# motorModule.net
KiCad netlist of a schematic drawn in EAGLE
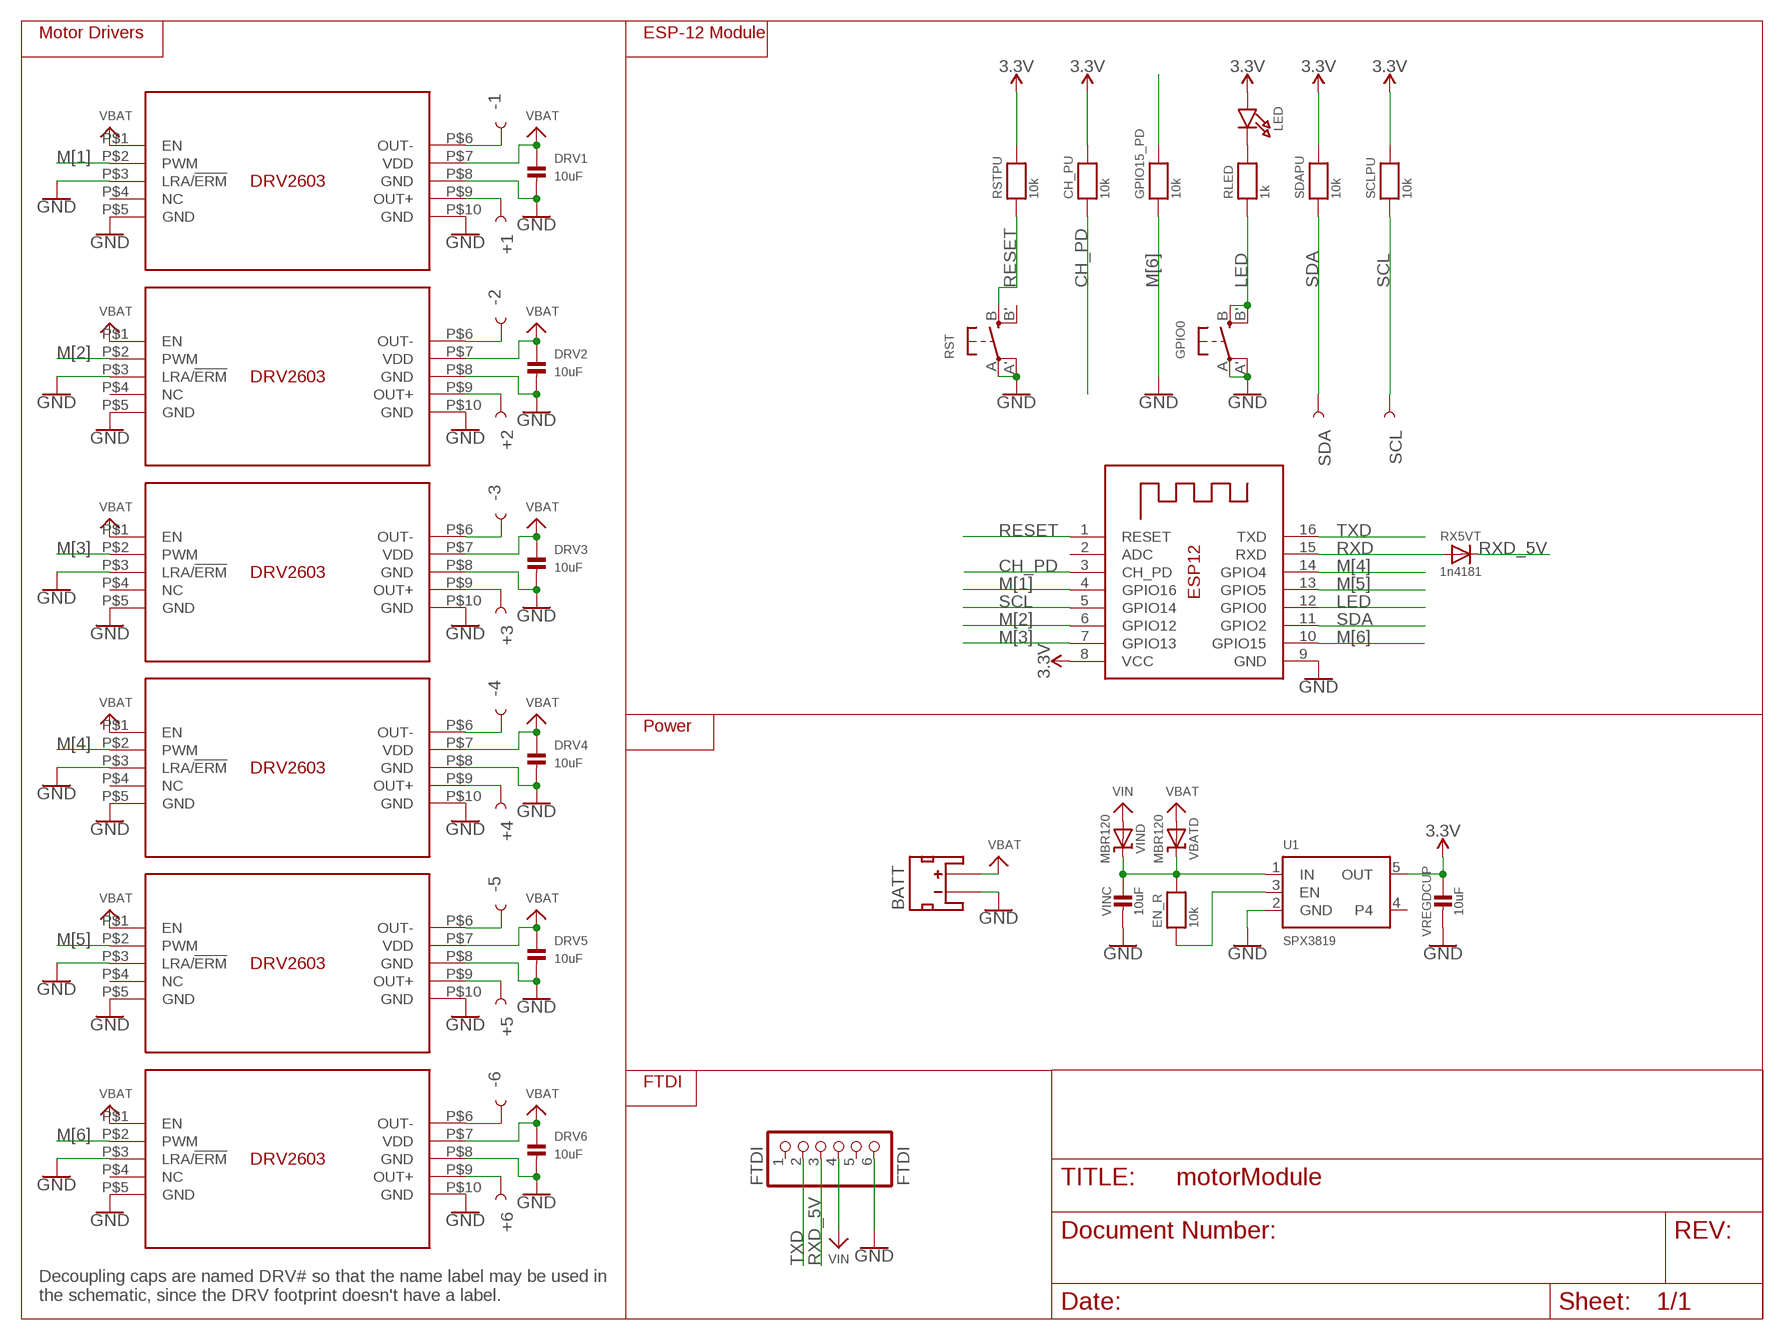
[diagram p0: schematic, sheet 1]

(export (version "E")
  (design (tool "Eeschema 10.0.6"))
  (components
    (comp (ref "+1")
      (value "SEWTAP_SMALL-2SIDE")
      (footprint "eagle-import:PETAL-SMALL-2SIDE")
      (libsource (lib "eagle-import") (part "SEWTAP_SMALL-2SIDE"))
    )
    (comp (ref "+2")
      (value "SEWTAP_SMALL-2SIDE")
      (footprint "eagle-import:PETAL-SMALL-2SIDE")
      (libsource (lib "eagle-import") (part "SEWTAP_SMALL-2SIDE"))
    )
    (comp (ref "+3")
      (value "SEWTAP_SMALL-2SIDE")
      (footprint "eagle-import:PETAL-SMALL-2SIDE")
      (libsource (lib "eagle-import") (part "SEWTAP_SMALL-2SIDE"))
    )
    (comp (ref "+4")
      (value "SEWTAP_SMALL-2SIDE")
      (footprint "eagle-import:PETAL-SMALL-2SIDE")
      (libsource (lib "eagle-import") (part "SEWTAP_SMALL-2SIDE"))
    )
    (comp (ref "+5")
      (value "SEWTAP_SMALL-2SIDE")
      (footprint "eagle-import:PETAL-SMALL-2SIDE")
      (libsource (lib "eagle-import") (part "SEWTAP_SMALL-2SIDE"))
    )
    (comp (ref "+6")
      (value "SEWTAP_SMALL-2SIDE")
      (footprint "eagle-import:PETAL-SMALL-2SIDE")
      (libsource (lib "eagle-import") (part "SEWTAP_SMALL-2SIDE"))
    )
    (comp (ref "-1")
      (value "SEWTAP_SMALL-2SIDE")
      (footprint "eagle-import:PETAL-SMALL-2SIDE")
      (libsource (lib "eagle-import") (part "SEWTAP_SMALL-2SIDE"))
    )
    (comp (ref "-2")
      (value "SEWTAP_SMALL-2SIDE")
      (footprint "eagle-import:PETAL-SMALL-2SIDE")
      (libsource (lib "eagle-import") (part "SEWTAP_SMALL-2SIDE"))
    )
    (comp (ref "-3")
      (value "SEWTAP_SMALL-2SIDE")
      (footprint "eagle-import:PETAL-SMALL-2SIDE")
      (libsource (lib "eagle-import") (part "SEWTAP_SMALL-2SIDE"))
    )
    (comp (ref "-4")
      (value "SEWTAP_SMALL-2SIDE")
      (footprint "eagle-import:PETAL-SMALL-2SIDE")
      (libsource (lib "eagle-import") (part "SEWTAP_SMALL-2SIDE"))
    )
    (comp (ref "-5")
      (value "SEWTAP_SMALL-2SIDE")
      (footprint "eagle-import:PETAL-SMALL-2SIDE")
      (libsource (lib "eagle-import") (part "SEWTAP_SMALL-2SIDE"))
    )
    (comp (ref "-6")
      (value "SEWTAP_SMALL-2SIDE")
      (footprint "eagle-import:PETAL-SMALL-2SIDE")
      (libsource (lib "eagle-import") (part "SEWTAP_SMALL-2SIDE"))
    )
    (comp (ref "BATT")
      (value "JST_2MM_MALE")
      (footprint "eagle-import:JST-2-SMD")
      (libsource (lib "eagle-import") (part "JST_2MM_MALE"))
    )
    (comp (ref "CH_PU")
      (value "10k")
      (footprint "eagle-import:0603")
      (libsource (lib "eagle-import") (part "RESISTOR0603"))
    )
    (comp (ref "DRV1")
      (value "10uF")
      (footprint "eagle-import:0603")
      (libsource (lib "eagle-import") (part "CAP_CERAMIC0603"))
    )
    (comp (ref "DRV2")
      (value "10uF")
      (footprint "eagle-import:0603")
      (libsource (lib "eagle-import") (part "CAP_CERAMIC0603"))
    )
    (comp (ref "DRV3")
      (value "10uF")
      (footprint "eagle-import:0603")
      (libsource (lib "eagle-import") (part "CAP_CERAMIC0603"))
    )
    (comp (ref "DRV4")
      (value "10uF")
      (footprint "eagle-import:0603")
      (libsource (lib "eagle-import") (part "CAP_CERAMIC0603"))
    )
    (comp (ref "DRV5")
      (value "10uF")
      (footprint "eagle-import:0603")
      (libsource (lib "eagle-import") (part "CAP_CERAMIC0603"))
    )
    (comp (ref "DRV6")
      (value "10uF")
      (footprint "eagle-import:0603")
      (libsource (lib "eagle-import") (part "CAP_CERAMIC0603"))
    )
    (comp (ref "DRVIC1")
      (value "DRV2603")
      (footprint "eagle-import:DRV2603")
      (libsource (lib "eagle-import") (part "DRV2603"))
    )
    (comp (ref "DRVIC2")
      (value "DRV2603")
      (footprint "eagle-import:DRV2603")
      (libsource (lib "eagle-import") (part "DRV2603"))
    )
    (comp (ref "DRVIC3")
      (value "DRV2603")
      (footprint "eagle-import:DRV2603")
      (libsource (lib "eagle-import") (part "DRV2603"))
    )
    (comp (ref "DRVIC4")
      (value "DRV2603")
      (footprint "eagle-import:DRV2603")
      (libsource (lib "eagle-import") (part "DRV2603"))
    )
    (comp (ref "DRVIC5")
      (value "DRV2603")
      (footprint "eagle-import:DRV2603")
      (libsource (lib "eagle-import") (part "DRV2603"))
    )
    (comp (ref "DRVIC6")
      (value "DRV2603")
      (footprint "eagle-import:DRV2603")
      (libsource (lib "eagle-import") (part "DRV2603"))
    )
    (comp (ref "EN_R")
      (value "10k")
      (footprint "eagle-import:0603")
      (libsource (lib "eagle-import") (part "RESISTOR0603"))
    )
    (comp (ref "ESP12")
      (value "ESP-12")
      (footprint "eagle-import:ESP-12")
      (libsource (lib "eagle-import") (part "ESP-12"))
    )
    (comp (ref "FTDI")
      (value "FTDI")
      (footprint "eagle-import:1X06")
      (libsource (lib "eagle-import") (part "PINHD-1X6"))
    )
    (comp (ref "GPIO0")
      (value "SWITCH_TACT_SMT4.6X2.8")
      (footprint "eagle-import:BTN_KMR2_4.6X2.8")
      (libsource (lib "eagle-import") (part "SWITCH_TACT_SMT4.6X2.8"))
    )
    (comp (ref "GPIO15_PD")
      (value "10k")
      (footprint "eagle-import:0603")
      (libsource (lib "eagle-import") (part "RESISTOR0603"))
    )
    (comp (ref "LED")
      (value "MICROBUILDER_LED0805")
      (footprint "eagle-import:MICROBUILDER_CHIPLED_0805")
      (libsource (lib "eagle-import") (part "MICROBUILDER_LED0805"))
    )
    (comp (ref "RLED")
      (value "1k")
      (footprint "eagle-import:0603")
      (libsource (lib "eagle-import") (part "RESISTOR0603"))
    )
    (comp (ref "RST")
      (value "SWITCH_TACT_SMT4.6X2.8")
      (footprint "eagle-import:BTN_KMR2_4.6X2.8")
      (libsource (lib "eagle-import") (part "SWITCH_TACT_SMT4.6X2.8"))
    )
    (comp (ref "RSTPU")
      (value "10k")
      (footprint "eagle-import:0603")
      (libsource (lib "eagle-import") (part "RESISTOR0603"))
    )
    (comp (ref "RX5VT")
      (value "1n4181")
      (footprint "eagle-import:MICROBUILDER_SOD-323")
      (libsource (lib "eagle-import") (part "MICROBUILDER_DIODESOD-323"))
    )
    (comp (ref "SCL")
      (value "SEWTAP_SMALL-2SIDE")
      (footprint "eagle-import:PETAL-SMALL-2SIDE")
      (libsource (lib "eagle-import") (part "SEWTAP_SMALL-2SIDE"))
    )
    (comp (ref "SCLPU")
      (value "10k")
      (footprint "eagle-import:0603")
      (libsource (lib "eagle-import") (part "RESISTOR0603"))
    )
    (comp (ref "SDA")
      (value "SEWTAP_SMALL-2SIDE")
      (footprint "eagle-import:PETAL-SMALL-2SIDE")
      (libsource (lib "eagle-import") (part "SEWTAP_SMALL-2SIDE"))
    )
    (comp (ref "SDAPU")
      (value "10k")
      (footprint "eagle-import:0603")
      (libsource (lib "eagle-import") (part "RESISTOR0603"))
    )
    (comp (ref "U1")
      (value "SPX3819")
      (footprint "eagle-import:SOT23-5")
      (libsource (lib "eagle-import") (part "VREG_SOT23-5"))
    )
    (comp (ref "VBATD")
      (value "MBR120")
      (footprint "eagle-import:MICROBUILDER_SOD-123")
      (libsource (lib "eagle-import") (part "MICROBUILDER_DIODE-SCHOTTKYSOD-123"))
    )
    (comp (ref "VINC")
      (value "10uF")
      (footprint "eagle-import:MICROBUILDER_0805-NO")
      (libsource (lib "eagle-import") (part "MICROBUILDER_CAP_CERAMIC0805-NOOUTLINE"))
    )
    (comp (ref "VIND")
      (value "MBR120")
      (footprint "eagle-import:MICROBUILDER_SOD-123")
      (libsource (lib "eagle-import") (part "MICROBUILDER_DIODE-SCHOTTKYSOD-123"))
    )
    (comp (ref "VREGDCUP")
      (value "10uF")
      (footprint "eagle-import:MICROBUILDER_0805-NO")
      (libsource (lib "eagle-import") (part "MICROBUILDER_CAP_CERAMIC0805-NOOUTLINE"))
    )
  )
  (nets
    (net (code "1") (name "/CH_PD") (class "Default")
      (node (ref "CH_PU") (pin "1") (pinfunction "1_1") (pintype "passive"))
      (node (ref "ESP12") (pin "3") (pinfunction "CH_PD_3") (pintype "input"))
    )
    (net (code "2") (name "/LED") (class "Default")
      (node (ref "ESP12") (pin "12") (pinfunction "GPIO0_12") (pintype "bidirectional"))
      (node (ref "GPIO0") (pin "B") (pinfunction "S_B") (pintype "passive"))
      (node (ref "GPIO0") (pin "B'") (pinfunction "S1_B'") (pintype "passive"))
      (node (ref "RLED") (pin "1") (pinfunction "1_1") (pintype "passive"))
    )
    (net (code "3") (name "/M[1]") (class "Default")
      (node (ref "DRVIC1") (pin "P$2") (pinfunction "PWM_P$2") (pintype "bidirectional"))
      (node (ref "ESP12") (pin "4") (pinfunction "GPIO16_4") (pintype "bidirectional"))
    )
    (net (code "4") (name "/M[2]") (class "Default")
      (node (ref "DRVIC2") (pin "P$2") (pinfunction "PWM_P$2") (pintype "bidirectional"))
      (node (ref "ESP12") (pin "6") (pinfunction "GPIO12_6") (pintype "bidirectional"))
    )
    (net (code "5") (name "/M[3]") (class "Default")
      (node (ref "DRVIC3") (pin "P$2") (pinfunction "PWM_P$2") (pintype "bidirectional"))
      (node (ref "ESP12") (pin "7") (pinfunction "GPIO13_7") (pintype "bidirectional"))
    )
    (net (code "6") (name "/M[4]") (class "Default")
      (node (ref "DRVIC4") (pin "P$2") (pinfunction "PWM_P$2") (pintype "bidirectional"))
      (node (ref "ESP12") (pin "14") (pinfunction "GPIO4_14") (pintype "bidirectional"))
    )
    (net (code "7") (name "/M[5]") (class "Default")
      (node (ref "DRVIC5") (pin "P$2") (pinfunction "PWM_P$2") (pintype "bidirectional"))
      (node (ref "ESP12") (pin "13") (pinfunction "GPIO5_13") (pintype "bidirectional"))
    )
    (net (code "8") (name "/M[6]") (class "Default")
      (node (ref "DRVIC6") (pin "P$2") (pinfunction "PWM_P$2") (pintype "bidirectional"))
      (node (ref "ESP12") (pin "10") (pinfunction "GPIO15_10") (pintype "bidirectional"))
      (node (ref "GPIO15_PD") (pin "2") (pinfunction "2_2") (pintype "passive"))
    )
    (net (code "9") (name "/RESET") (class "Default")
      (node (ref "ESP12") (pin "1") (pinfunction "RESET_1") (pintype "input"))
      (node (ref "RST") (pin "B") (pinfunction "S_B") (pintype "passive"))
      (node (ref "RSTPU") (pin "1") (pinfunction "1_1") (pintype "passive"))
    )
    (net (code "10") (name "/RXD") (class "Default")
      (node (ref "ESP12") (pin "15") (pinfunction "RXD_15") (pintype "input"))
      (node (ref "RX5VT") (pin "A") (pinfunction "A_A") (pintype "passive"))
    )
    (net (code "11") (name "/RXD_5V") (class "Default")
      (node (ref "FTDI") (pin "3") (pinfunction "3_3") (pintype "passive"))
      (node (ref "RX5VT") (pin "C") (pinfunction "C_C") (pintype "passive"))
    )
    (net (code "12") (name "/SCL") (class "Default")
      (node (ref "ESP12") (pin "5") (pinfunction "GPIO14_5") (pintype "bidirectional"))
      (node (ref "SCL") (pin "1") (pinfunction "1_1") (pintype "bidirectional"))
      (node (ref "SCLPU") (pin "1") (pinfunction "1_1") (pintype "passive"))
    )
    (net (code "13") (name "/SDA") (class "Default")
      (node (ref "ESP12") (pin "11") (pinfunction "GPIO2_11") (pintype "bidirectional"))
      (node (ref "SDA") (pin "1") (pinfunction "1_1") (pintype "bidirectional"))
      (node (ref "SDAPU") (pin "1") (pinfunction "1_1") (pintype "passive"))
    )
    (net (code "14") (name "/TXD") (class "Default")
      (node (ref "ESP12") (pin "16") (pinfunction "TXD_16") (pintype "output"))
      (node (ref "FTDI") (pin "2") (pinfunction "2_2") (pintype "passive"))
    )
    (net (code "15") (name "3.3V") (class "Default")
      (node (ref "CH_PU") (pin "2") (pinfunction "2_2") (pintype "passive"))
      (node (ref "ESP12") (pin "8") (pinfunction "VCC_8") (pintype "power_in"))
      (node (ref "LED") (pin "A") (pinfunction "A_A") (pintype "passive"))
      (node (ref "RSTPU") (pin "2") (pinfunction "2_2") (pintype "passive"))
      (node (ref "SCLPU") (pin "2") (pinfunction "2_2") (pintype "passive"))
      (node (ref "SDAPU") (pin "2") (pinfunction "2_2") (pintype "passive"))
      (node (ref "U1") (pin "5") (pinfunction "OUT_5") (pintype "bidirectional"))
      (node (ref "VREGDCUP") (pin "1") (pinfunction "1_1") (pintype "passive"))
    )
    (net (code "16") (name "GND") (class "Default")
      (node (ref "BATT") (pin "1") (pinfunction "-_1") (pintype "bidirectional"))
      (node (ref "DRV1") (pin "2") (pinfunction "P$2_2") (pintype "passive"))
      (node (ref "DRV2") (pin "2") (pinfunction "P$2_2") (pintype "passive"))
      (node (ref "DRV3") (pin "2") (pinfunction "P$2_2") (pintype "passive"))
      (node (ref "DRV4") (pin "2") (pinfunction "P$2_2") (pintype "passive"))
      (node (ref "DRV5") (pin "2") (pinfunction "P$2_2") (pintype "passive"))
      (node (ref "DRV6") (pin "2") (pinfunction "P$2_2") (pintype "passive"))
      (node (ref "DRVIC1") (pin "P$10") (pinfunction "GND_P$10") (pintype "bidirectional"))
      (node (ref "DRVIC1") (pin "P$3") (pinfunction "LRA/~{ERM}_P$3") (pintype "bidirectional"))
      (node (ref "DRVIC1") (pin "P$5") (pinfunction "GND_P$5") (pintype "bidirectional"))
      (node (ref "DRVIC1") (pin "P$8") (pinfunction "GND_P$8") (pintype "bidirectional"))
      (node (ref "DRVIC2") (pin "P$10") (pinfunction "GND_P$10") (pintype "bidirectional"))
      (node (ref "DRVIC2") (pin "P$3") (pinfunction "LRA/~{ERM}_P$3") (pintype "bidirectional"))
      (node (ref "DRVIC2") (pin "P$5") (pinfunction "GND_P$5") (pintype "bidirectional"))
      (node (ref "DRVIC2") (pin "P$8") (pinfunction "GND_P$8") (pintype "bidirectional"))
      (node (ref "DRVIC3") (pin "P$10") (pinfunction "GND_P$10") (pintype "bidirectional"))
      (node (ref "DRVIC3") (pin "P$3") (pinfunction "LRA/~{ERM}_P$3") (pintype "bidirectional"))
      (node (ref "DRVIC3") (pin "P$5") (pinfunction "GND_P$5") (pintype "bidirectional"))
      (node (ref "DRVIC3") (pin "P$8") (pinfunction "GND_P$8") (pintype "bidirectional"))
      (node (ref "DRVIC4") (pin "P$10") (pinfunction "GND_P$10") (pintype "bidirectional"))
      (node (ref "DRVIC4") (pin "P$3") (pinfunction "LRA/~{ERM}_P$3") (pintype "bidirectional"))
      (node (ref "DRVIC4") (pin "P$5") (pinfunction "GND_P$5") (pintype "bidirectional"))
      (node (ref "DRVIC4") (pin "P$8") (pinfunction "GND_P$8") (pintype "bidirectional"))
      (node (ref "DRVIC5") (pin "P$10") (pinfunction "GND_P$10") (pintype "bidirectional"))
      (node (ref "DRVIC5") (pin "P$3") (pinfunction "LRA/~{ERM}_P$3") (pintype "bidirectional"))
      (node (ref "DRVIC5") (pin "P$5") (pinfunction "GND_P$5") (pintype "bidirectional"))
      (node (ref "DRVIC5") (pin "P$8") (pinfunction "GND_P$8") (pintype "bidirectional"))
      (node (ref "DRVIC6") (pin "P$10") (pinfunction "GND_P$10") (pintype "bidirectional"))
      (node (ref "DRVIC6") (pin "P$3") (pinfunction "LRA/~{ERM}_P$3") (pintype "bidirectional"))
      (node (ref "DRVIC6") (pin "P$5") (pinfunction "GND_P$5") (pintype "bidirectional"))
      (node (ref "DRVIC6") (pin "P$8") (pinfunction "GND_P$8") (pintype "bidirectional"))
      (node (ref "ESP12") (pin "9") (pinfunction "GND_9") (pintype "power_in"))
      (node (ref "FTDI") (pin "6") (pinfunction "6_6") (pintype "passive"))
      (node (ref "GPIO0") (pin "A") (pinfunction "P_A") (pintype "passive"))
      (node (ref "GPIO0") (pin "A'") (pinfunction "P1_A'") (pintype "passive"))
      (node (ref "GPIO15_PD") (pin "1") (pinfunction "1_1") (pintype "passive"))
      (node (ref "RST") (pin "A") (pinfunction "P_A") (pintype "passive"))
      (node (ref "RST") (pin "A'") (pinfunction "P1_A'") (pintype "passive"))
      (node (ref "U1") (pin "2") (pinfunction "GND_2") (pintype "bidirectional"))
      (node (ref "VINC") (pin "2") (pinfunction "2_2") (pintype "passive"))
      (node (ref "VREGDCUP") (pin "2") (pinfunction "2_2") (pintype "passive"))
    )
    (net (code "17") (name "Net-(DRVIC1-OUT+)") (class "Default")
      (node (ref "+1") (pin "1") (pinfunction "1_1") (pintype "bidirectional"))
      (node (ref "DRVIC1") (pin "P$9") (pinfunction "OUT+_P$9") (pintype "bidirectional"))
    )
    (net (code "18") (name "Net-(DRVIC1-OUT-)") (class "Default")
      (node (ref "-1") (pin "1") (pinfunction "1_1") (pintype "bidirectional"))
      (node (ref "DRVIC1") (pin "P$6") (pinfunction "OUT-_P$6") (pintype "bidirectional"))
    )
    (net (code "19") (name "Net-(DRVIC2-OUT+)") (class "Default")
      (node (ref "+2") (pin "1") (pinfunction "1_1") (pintype "bidirectional"))
      (node (ref "DRVIC2") (pin "P$9") (pinfunction "OUT+_P$9") (pintype "bidirectional"))
    )
    (net (code "20") (name "Net-(DRVIC2-OUT-)") (class "Default")
      (node (ref "-2") (pin "1") (pinfunction "1_1") (pintype "bidirectional"))
      (node (ref "DRVIC2") (pin "P$6") (pinfunction "OUT-_P$6") (pintype "bidirectional"))
    )
    (net (code "21") (name "Net-(DRVIC3-OUT+)") (class "Default")
      (node (ref "+3") (pin "1") (pinfunction "1_1") (pintype "bidirectional"))
      (node (ref "DRVIC3") (pin "P$9") (pinfunction "OUT+_P$9") (pintype "bidirectional"))
    )
    (net (code "22") (name "Net-(DRVIC3-OUT-)") (class "Default")
      (node (ref "-3") (pin "1") (pinfunction "1_1") (pintype "bidirectional"))
      (node (ref "DRVIC3") (pin "P$6") (pinfunction "OUT-_P$6") (pintype "bidirectional"))
    )
    (net (code "23") (name "Net-(DRVIC4-OUT+)") (class "Default")
      (node (ref "+4") (pin "1") (pinfunction "1_1") (pintype "bidirectional"))
      (node (ref "DRVIC4") (pin "P$9") (pinfunction "OUT+_P$9") (pintype "bidirectional"))
    )
    (net (code "24") (name "Net-(DRVIC4-OUT-)") (class "Default")
      (node (ref "-4") (pin "1") (pinfunction "1_1") (pintype "bidirectional"))
      (node (ref "DRVIC4") (pin "P$6") (pinfunction "OUT-_P$6") (pintype "bidirectional"))
    )
    (net (code "25") (name "Net-(DRVIC5-OUT+)") (class "Default")
      (node (ref "+5") (pin "1") (pinfunction "1_1") (pintype "bidirectional"))
      (node (ref "DRVIC5") (pin "P$9") (pinfunction "OUT+_P$9") (pintype "bidirectional"))
    )
    (net (code "26") (name "Net-(DRVIC5-OUT-)") (class "Default")
      (node (ref "-5") (pin "1") (pinfunction "1_1") (pintype "bidirectional"))
      (node (ref "DRVIC5") (pin "P$6") (pinfunction "OUT-_P$6") (pintype "bidirectional"))
    )
    (net (code "27") (name "Net-(DRVIC6-OUT+)") (class "Default")
      (node (ref "+6") (pin "1") (pinfunction "1_1") (pintype "bidirectional"))
      (node (ref "DRVIC6") (pin "P$9") (pinfunction "OUT+_P$9") (pintype "bidirectional"))
    )
    (net (code "28") (name "Net-(DRVIC6-OUT-)") (class "Default")
      (node (ref "-6") (pin "1") (pinfunction "1_1") (pintype "bidirectional"))
      (node (ref "DRVIC6") (pin "P$6") (pinfunction "OUT-_P$6") (pintype "bidirectional"))
    )
    (net (code "29") (name "Net-(LED-PadC)") (class "Default")
      (node (ref "LED") (pin "C") (pinfunction "C_C") (pintype "passive"))
      (node (ref "RLED") (pin "2") (pinfunction "2_2") (pintype "passive"))
    )
    (net (code "30") (name "Net-(U1-EN)") (class "Default")
      (node (ref "EN_R") (pin "1") (pinfunction "1_1") (pintype "passive"))
      (node (ref "U1") (pin "3") (pinfunction "EN_3") (pintype "bidirectional"))
    )
    (net (code "31") (name "Net-(U1-IN)") (class "Default")
      (node (ref "EN_R") (pin "2") (pinfunction "2_2") (pintype "passive"))
      (node (ref "U1") (pin "1") (pinfunction "IN_1") (pintype "bidirectional"))
      (node (ref "VBATD") (pin "C") (pinfunction "C_C") (pintype "passive"))
      (node (ref "VINC") (pin "1") (pinfunction "1_1") (pintype "passive"))
      (node (ref "VIND") (pin "C") (pinfunction "C_C") (pintype "passive"))
    )
    (net (code "32") (name "VBAT") (class "Default")
      (node (ref "BATT") (pin "2") (pinfunction "+_2") (pintype "bidirectional"))
      (node (ref "DRV1") (pin "1") (pinfunction "P$1_1") (pintype "passive"))
      (node (ref "DRV2") (pin "1") (pinfunction "P$1_1") (pintype "passive"))
      (node (ref "DRV3") (pin "1") (pinfunction "P$1_1") (pintype "passive"))
      (node (ref "DRV4") (pin "1") (pinfunction "P$1_1") (pintype "passive"))
      (node (ref "DRV5") (pin "1") (pinfunction "P$1_1") (pintype "passive"))
      (node (ref "DRV6") (pin "1") (pinfunction "P$1_1") (pintype "passive"))
      (node (ref "DRVIC1") (pin "P$1") (pinfunction "EN_P$1") (pintype "bidirectional"))
      (node (ref "DRVIC1") (pin "P$7") (pinfunction "VDD_P$7") (pintype "bidirectional"))
      (node (ref "DRVIC2") (pin "P$1") (pinfunction "EN_P$1") (pintype "bidirectional"))
      (node (ref "DRVIC2") (pin "P$7") (pinfunction "VDD_P$7") (pintype "bidirectional"))
      (node (ref "DRVIC3") (pin "P$1") (pinfunction "EN_P$1") (pintype "bidirectional"))
      (node (ref "DRVIC3") (pin "P$7") (pinfunction "VDD_P$7") (pintype "bidirectional"))
      (node (ref "DRVIC4") (pin "P$1") (pinfunction "EN_P$1") (pintype "bidirectional"))
      (node (ref "DRVIC4") (pin "P$7") (pinfunction "VDD_P$7") (pintype "bidirectional"))
      (node (ref "DRVIC5") (pin "P$1") (pinfunction "EN_P$1") (pintype "bidirectional"))
      (node (ref "DRVIC5") (pin "P$7") (pinfunction "VDD_P$7") (pintype "bidirectional"))
      (node (ref "DRVIC6") (pin "P$1") (pinfunction "EN_P$1") (pintype "bidirectional"))
      (node (ref "DRVIC6") (pin "P$7") (pinfunction "VDD_P$7") (pintype "bidirectional"))
      (node (ref "VBATD") (pin "A") (pinfunction "A_A") (pintype "passive"))
    )
    (net (code "33") (name "VIN") (class "Default")
      (node (ref "FTDI") (pin "4") (pinfunction "4_4") (pintype "passive"))
      (node (ref "VIND") (pin "A") (pinfunction "A_A") (pintype "passive"))
    )
    (net (code "34") (name "unconnected-(BATT-PAD1-PadNC1)") (class "Default")
      (node (ref "BATT") (pin "NC1") (pinfunction "PAD1_NC1") (pintype "bidirectional"))
    )
    (net (code "35") (name "unconnected-(BATT-PAD2-PadNC2)") (class "Default")
      (node (ref "BATT") (pin "NC2") (pinfunction "PAD2_NC2") (pintype "bidirectional"))
    )
    (net (code "36") (name "unconnected-(DRVIC1-NC-PadP$4)") (class "Default")
      (node (ref "DRVIC1") (pin "P$4") (pinfunction "NC_P$4") (pintype "bidirectional"))
    )
    (net (code "37") (name "unconnected-(DRVIC2-NC-PadP$4)") (class "Default")
      (node (ref "DRVIC2") (pin "P$4") (pinfunction "NC_P$4") (pintype "bidirectional"))
    )
    (net (code "38") (name "unconnected-(DRVIC3-NC-PadP$4)") (class "Default")
      (node (ref "DRVIC3") (pin "P$4") (pinfunction "NC_P$4") (pintype "bidirectional"))
    )
    (net (code "39") (name "unconnected-(DRVIC4-NC-PadP$4)") (class "Default")
      (node (ref "DRVIC4") (pin "P$4") (pinfunction "NC_P$4") (pintype "bidirectional"))
    )
    (net (code "40") (name "unconnected-(DRVIC5-NC-PadP$4)") (class "Default")
      (node (ref "DRVIC5") (pin "P$4") (pinfunction "NC_P$4") (pintype "bidirectional"))
    )
    (net (code "41") (name "unconnected-(DRVIC6-NC-PadP$4)") (class "Default")
      (node (ref "DRVIC6") (pin "P$4") (pinfunction "NC_P$4") (pintype "bidirectional"))
    )
    (net (code "42") (name "unconnected-(ESP12-ADC-Pad2)") (class "Default")
      (node (ref "ESP12") (pin "2") (pinfunction "ADC_2") (pintype "passive"))
    )
    (net (code "43") (name "unconnected-(FTDI-Pad1)") (class "Default")
      (node (ref "FTDI") (pin "1") (pinfunction "1_1") (pintype "passive"))
    )
    (net (code "44") (name "unconnected-(FTDI-Pad5)") (class "Default")
      (node (ref "FTDI") (pin "5") (pinfunction "5_5") (pintype "passive"))
    )
    (net (code "45") (name "unconnected-(RST-S1-PadB')") (class "Default")
      (node (ref "RST") (pin "B'") (pinfunction "S1_B'") (pintype "passive"))
    )
    (net (code "46") (name "unconnected-(U1-P4-Pad4)") (class "Default")
      (node (ref "U1") (pin "4") (pinfunction "P4_4") (pintype "bidirectional"))
    )
  )
)
